# SurfaceEEG_V1_2.net
KiCad netlist of a schematic drawn in EAGLE
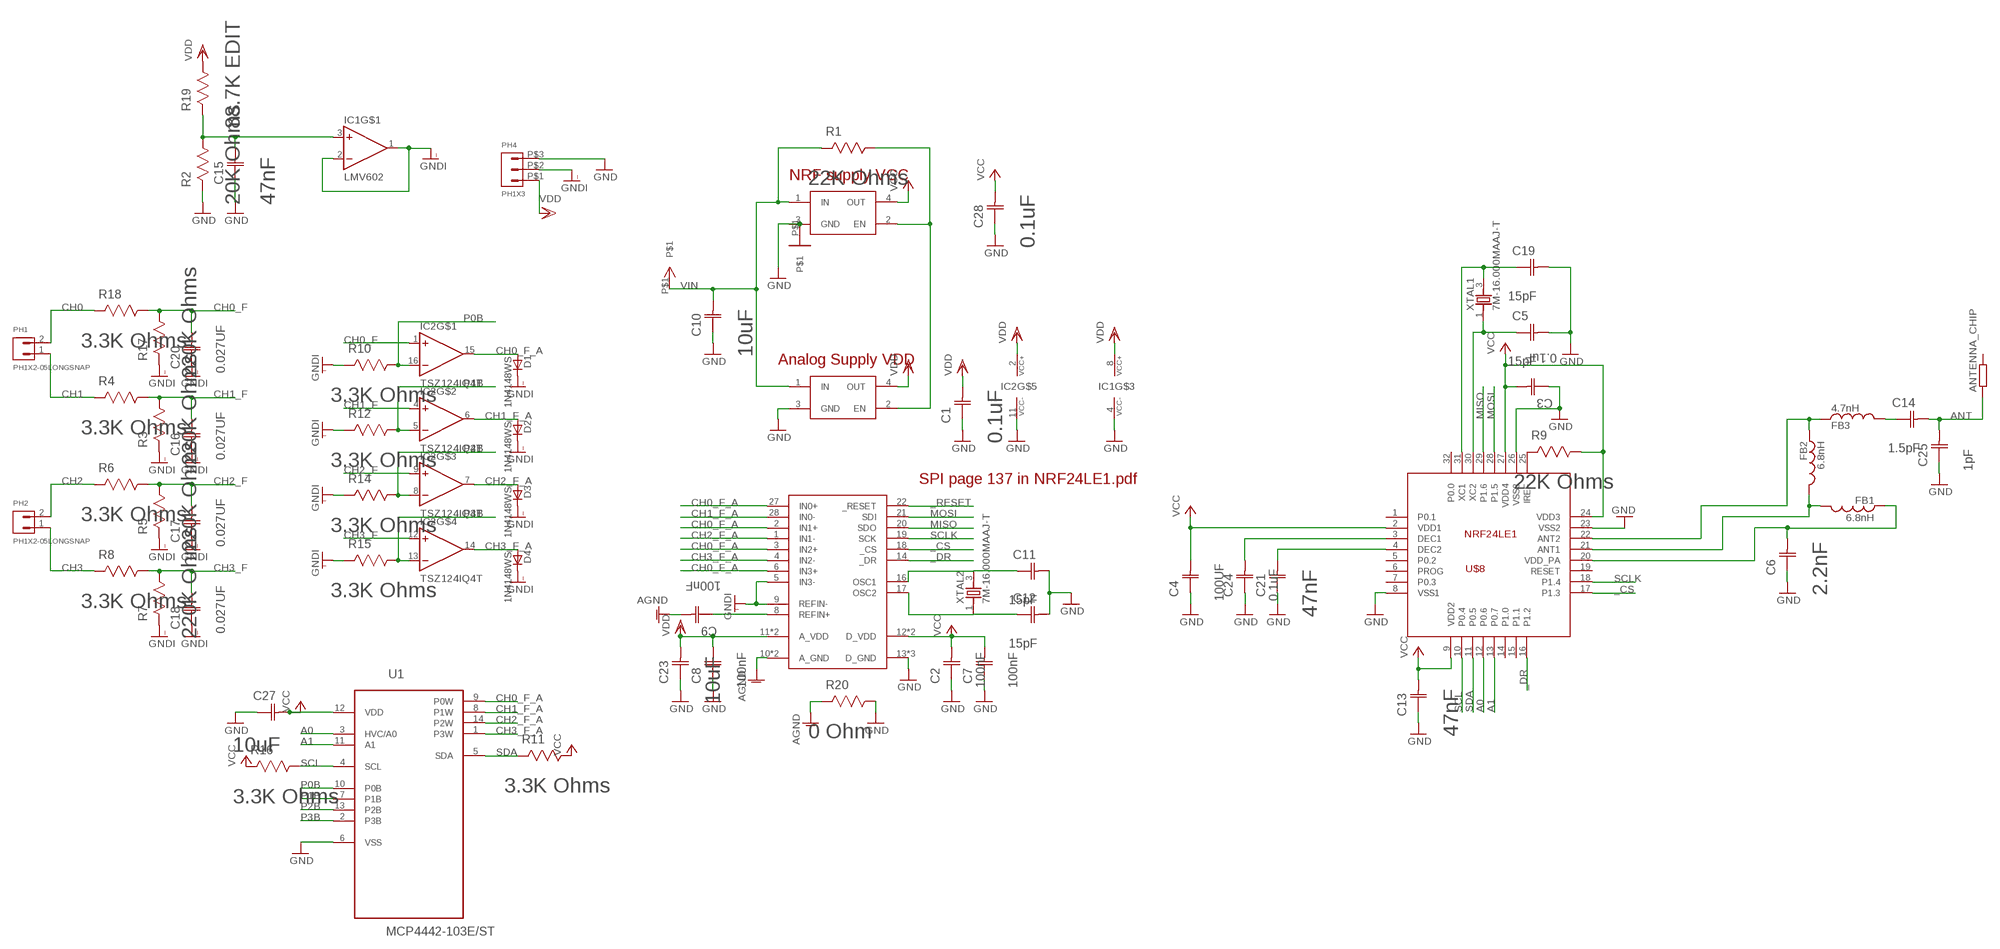
[diagram p0: schematic, sheet 1]

(export (version "E")
  (design (tool "Eeschema 10.0.6"))
  (components
    (comp (ref "ANTENNA_CHIP")
      (value "R0805")
      (footprint "eagle-import:R0805")
      (libsource (lib "eagle-import") (part "R0805"))
    )
    (comp (ref "C1")
      (value "0.1uF")
      (footprint "eagle-import:CAPC1608X85N")
      (fields (field (name "MPN") "C0603C104K5RAC-TU") (field (name "TOLERANCE") "±10%"))
      (libsource (lib "eagle-import") (part "C0603C104K5RAC-TU"))
    )
    (comp (ref "C2")
      (value "100nF")
      (footprint "eagle-import:CAPC1608X90N")
      (fields (field (name "MPN") "06033C104JAT2A") (field (name "TOLERANCE") "±5%"))
      (libsource (lib "eagle-import") (part "06033C104JAT2A"))
    )
    (comp (ref "C3")
      (value "0.1uF")
      (footprint "eagle-import:CAPC1005X60N")
      (fields (field (name "MPN") "04023C104KAT2A") (field (name "TOLERANCE") "±10%"))
      (libsource (lib "eagle-import") (part "04023C104KAT2A"))
    )
    (comp (ref "C4")
      (value "100UF")
      (footprint "eagle-import:CAPC3216X178N")
      (fields (field (name "MPN") "1206YD106MAT2A") (field (name "TOLERANCE") "±20%"))
      (libsource (lib "eagle-import") (part "1206YD106MAT2A"))
    )
    (comp (ref "C5")
      (value "15pF")
      (footprint "eagle-import:CAPC1005X60N")
      (fields (field (name "MPN") "UQCL2A150JAT2A/500") (field (name "TOLERANCE") "±5%"))
      (libsource (lib "eagle-import") (part "UQCL2A150JAT2A/500"))
    )
    (comp (ref "C6")
      (value "2.2nF")
      (footprint "eagle-import:CAPC1005X60N")
      (fields (field (name "MPN") "C0402C222K5RACTU") (field (name "TOLERANCE") "±10%"))
      (libsource (lib "eagle-import") (part "C0402C222K5RACTU"))
    )
    (comp (ref "C7")
      (value "100nF")
      (footprint "eagle-import:CAPC1608X90N")
      (fields (field (name "MPN") "06033C104JAT2A") (field (name "TOLERANCE") "±5%"))
      (libsource (lib "eagle-import") (part "06033C104JAT2A"))
    )
    (comp (ref "C8")
      (value "100nF")
      (footprint "eagle-import:CAPC1608X90N")
      (fields (field (name "MPN") "06033C104JAT2A") (field (name "TOLERANCE") "±5%"))
      (libsource (lib "eagle-import") (part "06033C104JAT2A"))
    )
    (comp (ref "C9")
      (value "100nF")
      (footprint "eagle-import:CAPC1608X90N")
      (fields (field (name "MPN") "06033C104JAT2A") (field (name "TOLERANCE") "±5%"))
      (libsource (lib "eagle-import") (part "06033C104JAT2A"))
    )
    (comp (ref "C10")
      (value "10uF")
      (footprint "eagle-import:CAPC1608X85N")
      (fields (field (name "MPN") "C0603C106M9PACTU") (field (name "TOLERANCE") "±20%"))
      (libsource (lib "eagle-import") (part "C0603C106M9PACTU"))
    )
    (comp (ref "C11")
      (value "15pF")
      (footprint "eagle-import:CAPC1005X60N")
      (fields (field (name "MPN") "UQCL2A150JAT2A/500") (field (name "TOLERANCE") "±5%"))
      (libsource (lib "eagle-import") (part "UQCL2A150JAT2A/500"))
    )
    (comp (ref "C12")
      (value "15pF")
      (footprint "eagle-import:CAPC1005X60N")
      (fields (field (name "MPN") "UQCL2A150JAT2A/500") (field (name "TOLERANCE") "±5%"))
      (libsource (lib "eagle-import") (part "UQCL2A150JAT2A/500"))
    )
    (comp (ref "C13")
      (value "47nF")
      (footprint "eagle-import:CAPC1608X85N")
      (fields (field (name "MPN") "C0603C473K1RACTU") (field (name "TOLERANCE") "±10%"))
      (libsource (lib "eagle-import") (part "C0603C473K1RACTU"))
    )
    (comp (ref "C14")
      (value "1.5pF")
      (footprint "eagle-import:CAPC1005X60N")
      (fields (field (name "MPN") "UQCL2A1R5BAT2A/500") (field (name "TOLERANCE") "±.1 pF"))
      (libsource (lib "eagle-import") (part "UQCL2A1R5BAT2A/500"))
    )
    (comp (ref "C15")
      (value "47nF")
      (footprint "eagle-import:CAPC1608X85N")
      (fields (field (name "MPN") "C0603C473K1RACTU") (field (name "TOLERANCE") "±10%"))
      (libsource (lib "eagle-import") (part "C0603C473K1RACTU"))
    )
    (comp (ref "C16")
      (value "0.027UF")
      (footprint "eagle-import:CAPC1608X90N")
      (fields (field (name "MPN") "0603YC273JAT2A") (field (name "TOLERANCE") "±5%"))
      (libsource (lib "eagle-import") (part "0603YC273JAT2A"))
    )
    (comp (ref "C17")
      (value "0.027UF")
      (footprint "eagle-import:CAPC1608X90N")
      (fields (field (name "MPN") "0603YC273JAT2A") (field (name "TOLERANCE") "±5%"))
      (libsource (lib "eagle-import") (part "0603YC273JAT2A"))
    )
    (comp (ref "C18")
      (value "0.027UF")
      (footprint "eagle-import:CAPC1608X90N")
      (fields (field (name "MPN") "0603YC273JAT2A") (field (name "TOLERANCE") "±5%"))
      (libsource (lib "eagle-import") (part "0603YC273JAT2A"))
    )
    (comp (ref "C19")
      (value "15pF")
      (footprint "eagle-import:CAPC1005X60N")
      (fields (field (name "MPN") "UQCL2A150JAT2A/500") (field (name "TOLERANCE") "±5%"))
      (libsource (lib "eagle-import") (part "UQCL2A150JAT2A/500"))
    )
    (comp (ref "C20")
      (value "0.027UF")
      (footprint "eagle-import:CAPC1608X90N")
      (fields (field (name "MPN") "0603YC273JAT2A") (field (name "TOLERANCE") "±5%"))
      (libsource (lib "eagle-import") (part "0603YC273JAT2A"))
    )
    (comp (ref "C21")
      (value "47nF")
      (footprint "eagle-import:CAPC1608X85N")
      (fields (field (name "MPN") "C0603C473K1RACTU") (field (name "TOLERANCE") "±10%"))
      (libsource (lib "eagle-import") (part "C0603C473K1RACTU"))
    )
    (comp (ref "C23")
      (value "10uF")
      (footprint "eagle-import:CAPC1608X85N")
      (fields (field (name "MPN") "C0603C106M9PACTU") (field (name "TOLERANCE") "±20%"))
      (libsource (lib "eagle-import") (part "C0603C106M9PACTU"))
    )
    (comp (ref "C24")
      (value "0.1uF")
      (footprint "eagle-import:CAPC1005X60N")
      (fields (field (name "MPN") "04023C104KAT2A") (field (name "TOLERANCE") "±10%"))
      (libsource (lib "eagle-import") (part "04023C104KAT2A"))
    )
    (comp (ref "C25")
      (value "1pF")
      (footprint "eagle-import:CAPC1005X60N")
      (fields (field (name "MPN") "UQCL2A1R0BAT2A/500") (field (name "TOLERANCE") "±.1 pF"))
      (libsource (lib "eagle-import") (part "UQCL2A1R0BAT2A/500"))
    )
    (comp (ref "C27")
      (value "10uF")
      (footprint "eagle-import:CAPC1608X85N")
      (fields (field (name "MPN") "C0603C106M9PACTU") (field (name "TOLERANCE") "±20%"))
      (libsource (lib "eagle-import") (part "C0603C106M9PACTU"))
    )
    (comp (ref "C28")
      (value "0.1uF")
      (footprint "eagle-import:CAPC1608X85N")
      (fields (field (name "MPN") "C0603C104K5RAC-TU") (field (name "TOLERANCE") "±10%"))
      (libsource (lib "eagle-import") (part "C0603C104K5RAC-TU"))
    )
    (comp (ref "D1")
      (value "1N4148WS")
      (footprint "eagle-import:SOD323F")
      (libsource (lib "eagle-import") (part "1N4148WS"))
    )
    (comp (ref "D2")
      (value "1N4148WS")
      (footprint "eagle-import:SOD323F")
      (libsource (lib "eagle-import") (part "1N4148WS"))
    )
    (comp (ref "D3")
      (value "1N4148WS")
      (footprint "eagle-import:SOD323F")
      (libsource (lib "eagle-import") (part "1N4148WS"))
    )
    (comp (ref "D4")
      (value "1N4148WS")
      (footprint "eagle-import:SOD323F")
      (libsource (lib "eagle-import") (part "1N4148WS"))
    )
    (comp (ref "FB1")
      (value "6.8nH")
      (footprint "eagle-import:FB0402")
      (libsource (lib "eagle-import") (part "FB0402"))
    )
    (comp (ref "FB2")
      (value "6.8nH")
      (footprint "eagle-import:FB0402")
      (libsource (lib "eagle-import") (part "FB0402"))
    )
    (comp (ref "FB3")
      (value "4.7nH")
      (footprint "eagle-import:FB0402")
      (libsource (lib "eagle-import") (part "FB0402"))
    )
    (comp (ref "IC1")
      (value "LMV602")
      (footprint "eagle-import:VSSOP8")
      (fields (field (name "MPN") "LMV602MM/NOPB"))
      (libsource (lib "eagle-import") (part "LMV602"))
    )
    (comp (ref "IC2")
      (value "TSZ124IQ4T")
      (footprint "eagle-import:QFN16")
      (libsource (lib "eagle-import") (part "TSZ124IQ4T"))
    )
    (comp (ref "PH1")
      (value "PH1X2-05LONGSNAP")
      (footprint "eagle-import:PHLS005-1-2")
      (libsource (lib "eagle-import") (part "PH1X2-05LONGSNAP"))
    )
    (comp (ref "PH2")
      (value "PH1X2-05LONGSNAP")
      (footprint "eagle-import:PHLS005-1-2")
      (libsource (lib "eagle-import") (part "PH1X2-05LONGSNAP"))
    )
    (comp (ref "PH4")
      (value "PH1X3")
      (footprint "eagle-import:PH005-1-3")
      (libsource (lib "eagle-import") (part "PH1X3"))
    )
    (comp (ref "R1")
      (value "22K Ohms")
      (footprint "eagle-import:RESC1608X60N")
      (fields (field (name "MPN") "RC0603FR-0722KL") (field (name "TOLERANCE") "±1%"))
      (libsource (lib "eagle-import") (part "RC0603FR-0722KL"))
    )
    (comp (ref "R2")
      (value "20K Ohms")
      (footprint "eagle-import:RESC1608X60N")
      (fields (field (name "MPN") "RC0603FR-0720KL") (field (name "TOLERANCE") "±1%"))
      (libsource (lib "eagle-import") (part "RC0603FR-0720KL"))
    )
    (comp (ref "R3")
      (value "220K Ohms")
      (footprint "eagle-import:RESC1608X60N")
      (fields (field (name "MPN") "RC0603FR-07220KL") (field (name "TOLERANCE") "±1%"))
      (libsource (lib "eagle-import") (part "RC0603FR-07220KL"))
    )
    (comp (ref "R4")
      (value "3.3K Ohms")
      (footprint "eagle-import:RESC1608X60N")
      (fields (field (name "MPN") "RC0603FR-073K3L") (field (name "TOLERANCE") "±1%"))
      (libsource (lib "eagle-import") (part "RC0603FR-073K3L"))
    )
    (comp (ref "R5")
      (value "220K Ohms")
      (footprint "eagle-import:RESC1608X60N")
      (fields (field (name "MPN") "RC0603FR-07220KL") (field (name "TOLERANCE") "±1%"))
      (libsource (lib "eagle-import") (part "RC0603FR-07220KL"))
    )
    (comp (ref "R6")
      (value "3.3K Ohms")
      (footprint "eagle-import:RESC1608X60N")
      (fields (field (name "MPN") "RC0603FR-073K3L") (field (name "TOLERANCE") "±1%"))
      (libsource (lib "eagle-import") (part "RC0603FR-073K3L"))
    )
    (comp (ref "R7")
      (value "220K Ohms")
      (footprint "eagle-import:RESC1608X60N")
      (fields (field (name "MPN") "RC0603FR-07220KL") (field (name "TOLERANCE") "±1%"))
      (libsource (lib "eagle-import") (part "RC0603FR-07220KL"))
    )
    (comp (ref "R8")
      (value "3.3K Ohms")
      (footprint "eagle-import:RESC1608X60N")
      (fields (field (name "MPN") "RC0603FR-073K3L") (field (name "TOLERANCE") "±1%"))
      (libsource (lib "eagle-import") (part "RC0603FR-073K3L"))
    )
    (comp (ref "R9")
      (value "22K Ohms")
      (footprint "eagle-import:RESC1608X60N")
      (fields (field (name "MPN") "RC0603FR-0722KL") (field (name "TOLERANCE") "±1%"))
      (libsource (lib "eagle-import") (part "RC0603FR-0722KL"))
    )
    (comp (ref "R10")
      (value "3.3K Ohms")
      (footprint "eagle-import:RESC1608X60N")
      (fields (field (name "MPN") "RC0603FR-073K3L") (field (name "TOLERANCE") "±1%"))
      (libsource (lib "eagle-import") (part "RC0603FR-073K3L"))
    )
    (comp (ref "R11")
      (value "3.3K Ohms")
      (footprint "eagle-import:RESC1608X60N")
      (fields (field (name "MPN") "RC0603FR-073K3L") (field (name "TOLERANCE") "±1%"))
      (libsource (lib "eagle-import") (part "RC0603FR-073K3L"))
    )
    (comp (ref "R12")
      (value "3.3K Ohms")
      (footprint "eagle-import:RESC1608X60N")
      (fields (field (name "MPN") "RC0603FR-073K3L") (field (name "TOLERANCE") "±1%"))
      (libsource (lib "eagle-import") (part "RC0603FR-073K3L"))
    )
    (comp (ref "R14")
      (value "3.3K Ohms")
      (footprint "eagle-import:RESC1608X60N")
      (fields (field (name "MPN") "RC0603FR-073K3L") (field (name "TOLERANCE") "±1%"))
      (libsource (lib "eagle-import") (part "RC0603FR-073K3L"))
    )
    (comp (ref "R15")
      (value "3.3K Ohms")
      (footprint "eagle-import:RESC1608X60N")
      (fields (field (name "MPN") "RC0603FR-073K3L") (field (name "TOLERANCE") "±1%"))
      (libsource (lib "eagle-import") (part "RC0603FR-073K3L"))
    )
    (comp (ref "R16")
      (value "3.3K Ohms")
      (footprint "eagle-import:RESC1608X60N")
      (fields (field (name "MPN") "RC0603FR-073K3L") (field (name "TOLERANCE") "±1%"))
      (libsource (lib "eagle-import") (part "RC0603FR-073K3L"))
    )
    (comp (ref "R17")
      (value "220K Ohms")
      (footprint "eagle-import:RESC1608X60N")
      (fields (field (name "MPN") "RC0603FR-07220KL") (field (name "TOLERANCE") "±1%"))
      (libsource (lib "eagle-import") (part "RC0603FR-07220KL"))
    )
    (comp (ref "R18")
      (value "3.3K Ohms")
      (footprint "eagle-import:RESC1608X60N")
      (fields (field (name "MPN") "RC0603FR-073K3L") (field (name "TOLERANCE") "±1%"))
      (libsource (lib "eagle-import") (part "RC0603FR-073K3L"))
    )
    (comp (ref "R19")
      (value "88.7K EDIT")
      (footprint "eagle-import:RESC1608X60N")
      (fields (field (name "MPN") "RT0603FRE0782KL") (field (name "TOLERANCE") "±1%"))
      (libsource (lib "eagle-import") (part "RT0603FRE0782KL"))
    )
    (comp (ref "R20")
      (value "0 Ohm")
      (footprint "eagle-import:RESC1608X60N")
      (fields (field (name "MPN") "9C06031A0R00JLHFT") (field (name "TOLERANCE") "±5%"))
      (libsource (lib "eagle-import") (part "9C06031A0R00JLHFT"))
    )
    (comp (ref "U$1")
      (value "NCP103")
      (footprint "eagle-import:UDFN4-1_1")
      (fields (field (name "MPN") "NCP103AMX330TCG"))
      (libsource (lib "eagle-import") (part "NCP103"))
    )
    (comp (ref "U$2")
      (value "NCP103")
      (footprint "eagle-import:UDFN4-1_1")
      (fields (field (name "MPN") "NCP103AMX330TCG"))
      (libsource (lib "eagle-import") (part "NCP103"))
    )
    (comp (ref "U$3")
      (value "MCP3912")
      (footprint "eagle-import:QFN28")
      (fields (field (name "MPN") "MCP3912A1-E/MQ "))
      (libsource (lib "eagle-import") (part "MCP3912"))
    )
    (comp (ref "U$4")
      (value "VCC")
      (footprint "eagle-import:VCC-PAD")
      (libsource (lib "eagle-import") (part "VCC"))
    )
    (comp (ref "U$5")
      (value "GND")
      (footprint "eagle-import:GND-PAD")
      (libsource (lib "eagle-import") (part "GND"))
    )
    (comp (ref "U$8")
      (value "NRF24LE1")
      (footprint "eagle-import:QFN-32")
      (fields (field (name "MPN") "NRF24LE1-F16Q24-T"))
      (libsource (lib "eagle-import") (part "NRF24LE1"))
    )
    (comp (ref "U1")
      (value "MCP4442-103E/ST")
      (footprint "eagle-import:SOP65P640X120-14N")
      (libsource (lib "eagle-import") (part "MCP4442-103E/ST"))
    )
    (comp (ref "XTAL1")
      (value "7M-16.000MAAJ-T")
      (footprint "eagle-import:TXC_7M-16.000MAAJ-T")
      (fields (field (name "MPN") "7M-16.000MAAJ-T "))
      (libsource (lib "eagle-import") (part "7M-16.000MAAJ-T"))
    )
    (comp (ref "XTAL2")
      (value "7M-16.000MAAJ-T")
      (footprint "eagle-import:TXC_7M-16.000MAAJ-T")
      (fields (field (name "MPN") "7M-16.000MAAJ-T "))
      (libsource (lib "eagle-import") (part "7M-16.000MAAJ-T"))
    )
  )
  (nets
    (net (code "1") (name "/A0") (class "Default")
      (node (ref "U$8") (pin "12") (pinfunction "P0.6_12") (pintype "bidirectional"))
      (node (ref "U1") (pin "3") (pinfunction "HVC/A0_3") (pintype "input"))
    )
    (net (code "2") (name "/A1") (class "Default")
      (node (ref "U$8") (pin "13") (pinfunction "P0.7_13") (pintype "bidirectional"))
      (node (ref "U1") (pin "11") (pinfunction "A1_11") (pintype "input"))
    )
    (net (code "3") (name "/ANT") (class "Default")
      (node (ref "ANTENNA_CHIP") (pin "1") (pinfunction "1_1") (pintype "passive"))
      (node (ref "C14") (pin "1") (pinfunction "C2_1") (pintype "passive"))
      (node (ref "C25") (pin "1") (pinfunction "C2_1") (pintype "passive"))
    )
    (net (code "4") (name "/CH0") (class "Default")
      (node (ref "PH1") (pin "2") (pinfunction "2_2") (pintype "bidirectional"))
      (node (ref "R18") (pin "2") (pinfunction "R2_2") (pintype "passive"))
    )
    (net (code "5") (name "/CH0_F") (class "Default")
      (node (ref "C20") (pin "2") (pinfunction "C2_2") (pintype "passive"))
      (node (ref "IC2") (pin "1") (pinfunction "IN+_1") (pintype "input"))
      (node (ref "R17") (pin "1") (pinfunction "R1_1") (pintype "passive"))
      (node (ref "R18") (pin "1") (pinfunction "R1_1") (pintype "passive"))
    )
    (net (code "6") (name "/CH0_F_A") (class "Default")
      (node (ref "D1") (pin "A") (pinfunction "A_A") (pintype "passive"))
      (node (ref "IC2") (pin "15") (pinfunction "OUT_15") (pintype "output"))
      (node (ref "U$3") (pin "2") (pinfunction "IN1+_2") (pintype "bidirectional"))
      (node (ref "U$3") (pin "27") (pinfunction "IN0+_27") (pintype "bidirectional"))
      (node (ref "U$3") (pin "3") (pinfunction "IN2+_3") (pintype "bidirectional"))
      (node (ref "U$3") (pin "6") (pinfunction "IN3+_6") (pintype "bidirectional"))
      (node (ref "U1") (pin "9") (pinfunction "P0W_9") (pintype "passive"))
    )
    (net (code "7") (name "/CH1") (class "Default")
      (node (ref "PH1") (pin "1") (pinfunction "1_1") (pintype "bidirectional"))
      (node (ref "R4") (pin "2") (pinfunction "R2_2") (pintype "passive"))
    )
    (net (code "8") (name "/CH1_F") (class "Default")
      (node (ref "C16") (pin "2") (pinfunction "C2_2") (pintype "passive"))
      (node (ref "IC2") (pin "4") (pinfunction "IN+_4") (pintype "input"))
      (node (ref "R3") (pin "1") (pinfunction "R1_1") (pintype "passive"))
      (node (ref "R4") (pin "1") (pinfunction "R1_1") (pintype "passive"))
    )
    (net (code "9") (name "/CH1_F_A") (class "Default")
      (node (ref "D2") (pin "A") (pinfunction "A_A") (pintype "passive"))
      (node (ref "IC2") (pin "6") (pinfunction "OUT_6") (pintype "output"))
      (node (ref "U$3") (pin "28") (pinfunction "IN0-_28") (pintype "bidirectional"))
      (node (ref "U1") (pin "8") (pinfunction "P1W_8") (pintype "passive"))
    )
    (net (code "10") (name "/CH2") (class "Default")
      (node (ref "PH2") (pin "2") (pinfunction "2_2") (pintype "bidirectional"))
      (node (ref "R6") (pin "2") (pinfunction "R2_2") (pintype "passive"))
    )
    (net (code "11") (name "/CH2_F") (class "Default")
      (node (ref "C17") (pin "2") (pinfunction "C2_2") (pintype "passive"))
      (node (ref "IC2") (pin "9") (pinfunction "IN+_9") (pintype "input"))
      (node (ref "R5") (pin "1") (pinfunction "R1_1") (pintype "passive"))
      (node (ref "R6") (pin "1") (pinfunction "R1_1") (pintype "passive"))
    )
    (net (code "12") (name "/CH2_F_A") (class "Default")
      (node (ref "D3") (pin "A") (pinfunction "A_A") (pintype "passive"))
      (node (ref "IC2") (pin "7") (pinfunction "OUT_7") (pintype "output"))
      (node (ref "U$3") (pin "1") (pinfunction "IN1-_1") (pintype "bidirectional"))
      (node (ref "U1") (pin "14") (pinfunction "P2W_14") (pintype "passive"))
    )
    (net (code "13") (name "/CH3") (class "Default")
      (node (ref "PH2") (pin "1") (pinfunction "1_1") (pintype "bidirectional"))
      (node (ref "R8") (pin "2") (pinfunction "R2_2") (pintype "passive"))
    )
    (net (code "14") (name "/CH3_F") (class "Default")
      (node (ref "C18") (pin "2") (pinfunction "C2_2") (pintype "passive"))
      (node (ref "IC2") (pin "12") (pinfunction "IN+_12") (pintype "input"))
      (node (ref "R7") (pin "1") (pinfunction "R1_1") (pintype "passive"))
      (node (ref "R8") (pin "1") (pinfunction "R1_1") (pintype "passive"))
    )
    (net (code "15") (name "/CH3_F_A") (class "Default")
      (node (ref "D4") (pin "A") (pinfunction "A_A") (pintype "passive"))
      (node (ref "IC2") (pin "14") (pinfunction "OUT_14") (pintype "output"))
      (node (ref "U$3") (pin "4") (pinfunction "IN2-_4") (pintype "bidirectional"))
      (node (ref "U1") (pin "1") (pinfunction "P3W_1") (pintype "passive"))
    )
    (net (code "16") (name "/MISO") (class "Default")
      (node (ref "U$3") (pin "20") (pinfunction "SDO_20") (pintype "bidirectional"))
      (node (ref "U$8") (pin "29") (pinfunction "P1.6_29") (pintype "bidirectional"))
    )
    (net (code "17") (name "/MOSI") (class "Default")
      (node (ref "U$3") (pin "21") (pinfunction "SDI_21") (pintype "bidirectional"))
      (node (ref "U$8") (pin "28") (pinfunction "P1.5_28") (pintype "bidirectional"))
    )
    (net (code "18") (name "/P0B") (class "Default")
      (node (ref "IC2") (pin "16") (pinfunction "IN-_16") (pintype "input"))
      (node (ref "R10") (pin "1") (pinfunction "R1_1") (pintype "passive"))
      (node (ref "U1") (pin "10") (pinfunction "P0B_10") (pintype "passive"))
    )
    (net (code "19") (name "/P1B") (class "Default")
      (node (ref "IC2") (pin "5") (pinfunction "IN-_5") (pintype "input"))
      (node (ref "R12") (pin "1") (pinfunction "R1_1") (pintype "passive"))
      (node (ref "U1") (pin "7") (pinfunction "P1B_7") (pintype "passive"))
    )
    (net (code "20") (name "/P2B") (class "Default")
      (node (ref "IC2") (pin "8") (pinfunction "IN-_8") (pintype "input"))
      (node (ref "R14") (pin "1") (pinfunction "R1_1") (pintype "passive"))
      (node (ref "U1") (pin "13") (pinfunction "P2B_13") (pintype "passive"))
    )
    (net (code "21") (name "/P3B") (class "Default")
      (node (ref "IC2") (pin "13") (pinfunction "IN-_13") (pintype "input"))
      (node (ref "R15") (pin "1") (pinfunction "R1_1") (pintype "passive"))
      (node (ref "U1") (pin "2") (pinfunction "P3B_2") (pintype "passive"))
    )
    (net (code "22") (name "/SCL") (class "Default")
      (node (ref "R16") (pin "1") (pinfunction "R1_1") (pintype "passive"))
      (node (ref "U$8") (pin "10") (pinfunction "P0.4_10") (pintype "bidirectional"))
      (node (ref "U1") (pin "4") (pinfunction "SCL_4") (pintype "input"))
    )
    (net (code "23") (name "/SCLK") (class "Default")
      (node (ref "U$3") (pin "19") (pinfunction "SCK_19") (pintype "bidirectional"))
      (node (ref "U$8") (pin "18") (pinfunction "P1.4_18") (pintype "bidirectional"))
    )
    (net (code "24") (name "/SDA") (class "Default")
      (node (ref "R11") (pin "2") (pinfunction "R2_2") (pintype "passive"))
      (node (ref "U$8") (pin "11") (pinfunction "P0.5_11") (pintype "bidirectional"))
      (node (ref "U1") (pin "5") (pinfunction "SDA_5") (pintype "bidirectional"))
    )
    (net (code "25") (name "/VIN") (class "Default")
      (node (ref "C10") (pin "2") (pinfunction "C2_2") (pintype "passive"))
      (node (ref "R1") (pin "2") (pinfunction "R2_2") (pintype "passive"))
      (node (ref "U$1") (pin "1") (pinfunction "IN_1") (pintype "bidirectional"))
      (node (ref "U$2") (pin "1") (pinfunction "IN_1") (pintype "bidirectional"))
      (node (ref "U$4") (pin "P$1") (pinfunction "P$1_P$1") (pintype "bidirectional"))
    )
    (net (code "26") (name "/_CS") (class "Default")
      (node (ref "U$3") (pin "18") (pinfunction "_CS_18") (pintype "bidirectional"))
      (node (ref "U$8") (pin "17") (pinfunction "P1.3_17") (pintype "bidirectional"))
    )
    (net (code "27") (name "/_DR") (class "Default")
      (node (ref "U$3") (pin "14") (pinfunction "_DR_14") (pintype "bidirectional"))
      (node (ref "U$8") (pin "16") (pinfunction "P1.2_16") (pintype "bidirectional"))
    )
    (net (code "28") (name "/_RESET") (class "Default")
      (node (ref "U$3") (pin "22") (pinfunction "_RESET_22") (pintype "bidirectional"))
    )
    (net (code "29") (name "AGND") (class "Default")
      (node (ref "C9") (pin "2") (pinfunction "C2_2") (pintype "passive"))
      (node (ref "R20") (pin "2") (pinfunction "R2_2") (pintype "passive"))
      (node (ref "U$3") (pin "10") (pinfunction "A_GND_10") (pintype "bidirectional"))
      (node (ref "U$3") (pin "26") (pinfunction "A_GND_26") (pintype "bidirectional"))
    )
    (net (code "30") (name "GND") (class "Default")
      (node (ref "C1") (pin "1") (pinfunction "C1_1") (pintype "passive"))
      (node (ref "C10") (pin "1") (pinfunction "C1_1") (pintype "passive"))
      (node (ref "C11") (pin "1") (pinfunction "C2_1") (pintype "passive"))
      (node (ref "C12") (pin "1") (pinfunction "C2_1") (pintype "passive"))
      (node (ref "C13") (pin "1") (pinfunction "C1_1") (pintype "passive"))
      (node (ref "C15") (pin "1") (pinfunction "C1_1") (pintype "passive"))
      (node (ref "C19") (pin "1") (pinfunction "C2_1") (pintype "passive"))
      (node (ref "C2") (pin "1") (pinfunction "C1_1") (pintype "passive"))
      (node (ref "C21") (pin "1") (pinfunction "C1_1") (pintype "passive"))
      (node (ref "C23") (pin "1") (pinfunction "C1_1") (pintype "passive"))
      (node (ref "C24") (pin "2") (pinfunction "C1_2") (pintype "passive"))
      (node (ref "C25") (pin "2") (pinfunction "C1_2") (pintype "passive"))
      (node (ref "C27") (pin "1") (pinfunction "C1_1") (pintype "passive"))
      (node (ref "C28") (pin "1") (pinfunction "C1_1") (pintype "passive"))
      (node (ref "C3") (pin "2") (pinfunction "C1_2") (pintype "passive"))
      (node (ref "C4") (pin "1") (pinfunction "C1_1") (pintype "passive"))
      (node (ref "C5") (pin "1") (pinfunction "C2_1") (pintype "passive"))
      (node (ref "C6") (pin "1") (pinfunction "C1_1") (pintype "passive"))
      (node (ref "C7") (pin "1") (pinfunction "C1_1") (pintype "passive"))
      (node (ref "C8") (pin "1") (pinfunction "C1_1") (pintype "passive"))
      (node (ref "IC1") (pin "4") (pinfunction "VCC-_4") (pintype "power_in"))
      (node (ref "IC2") (pin "11") (pinfunction "VCC-_11") (pintype "power_in"))
      (node (ref "PH4") (pin "P$3") (pinfunction "3_P$3") (pintype "bidirectional"))
      (node (ref "R2") (pin "2") (pinfunction "R2_2") (pintype "passive"))
      (node (ref "R20") (pin "1") (pinfunction "R1_1") (pintype "passive"))
      (node (ref "U$1") (pin "3") (pinfunction "GND_3") (pintype "bidirectional"))
      (node (ref "U$2") (pin "3") (pinfunction "GND_3") (pintype "bidirectional"))
      (node (ref "U$3") (pin "13") (pinfunction "D_GND_13") (pintype "bidirectional"))
      (node (ref "U$3") (pin "15") (pinfunction "D_GND_15") (pintype "bidirectional"))
      (node (ref "U$3") (pin "23") (pinfunction "D_GND_23") (pintype "bidirectional"))
      (node (ref "U$5") (pin "P$1") (pinfunction "P$1_P$1") (pintype "bidirectional"))
      (node (ref "U$8") (pin "23") (pinfunction "VSS2_23") (pintype "bidirectional"))
      (node (ref "U$8") (pin "26") (pinfunction "VSS3_26") (pintype "bidirectional"))
      (node (ref "U$8") (pin "8") (pinfunction "VSS1_8") (pintype "bidirectional"))
      (node (ref "U1") (pin "6") (pinfunction "VSS_6") (pintype "power_in"))
    )
    (net (code "31") (name "GNDI") (class "Default")
      (node (ref "C16") (pin "1") (pinfunction "C1_1") (pintype "passive"))
      (node (ref "C17") (pin "1") (pinfunction "C1_1") (pintype "passive"))
      (node (ref "C18") (pin "1") (pinfunction "C1_1") (pintype "passive"))
      (node (ref "C20") (pin "1") (pinfunction "C1_1") (pintype "passive"))
      (node (ref "D1") (pin "C") (pinfunction "C_C") (pintype "passive"))
      (node (ref "D2") (pin "C") (pinfunction "C_C") (pintype "passive"))
      (node (ref "D3") (pin "C") (pinfunction "C_C") (pintype "passive"))
      (node (ref "D4") (pin "C") (pinfunction "C_C") (pintype "passive"))
      (node (ref "IC1") (pin "1") (pinfunction "OUT_1") (pintype "output"))
      (node (ref "IC1") (pin "2") (pinfunction "IN-_2") (pintype "input"))
      (node (ref "PH4") (pin "P$2") (pinfunction "2_P$2") (pintype "bidirectional"))
      (node (ref "R10") (pin "2") (pinfunction "R2_2") (pintype "passive"))
      (node (ref "R12") (pin "2") (pinfunction "R2_2") (pintype "passive"))
      (node (ref "R14") (pin "2") (pinfunction "R2_2") (pintype "passive"))
      (node (ref "R15") (pin "2") (pinfunction "R2_2") (pintype "passive"))
      (node (ref "R17") (pin "2") (pinfunction "R2_2") (pintype "passive"))
      (node (ref "R3") (pin "2") (pinfunction "R2_2") (pintype "passive"))
      (node (ref "R5") (pin "2") (pinfunction "R2_2") (pintype "passive"))
      (node (ref "R7") (pin "2") (pinfunction "R2_2") (pintype "passive"))
      (node (ref "U$3") (pin "5") (pinfunction "IN3-_5") (pintype "bidirectional"))
      (node (ref "U$3") (pin "9") (pinfunction "REFIN-_9") (pintype "bidirectional"))
    )
    (net (code "32") (name "Net-(C5-C1)") (class "Default")
      (node (ref "C5") (pin "2") (pinfunction "C1_2") (pintype "passive"))
      (node (ref "U$8") (pin "30") (pinfunction "XC2_30") (pintype "bidirectional"))
      (node (ref "XTAL1") (pin "1") (pinfunction "1_1") (pintype "passive"))
    )
    (net (code "33") (name "Net-(C6-C2)") (class "Default")
      (node (ref "C6") (pin "2") (pinfunction "C2_2") (pintype "passive"))
      (node (ref "FB1") (pin "1") (pinfunction "1_1") (pintype "passive"))
      (node (ref "U$8") (pin "20") (pinfunction "VDD_PA_20") (pintype "bidirectional"))
    )
    (net (code "34") (name "Net-(C9-C1)") (class "Default")
      (node (ref "C9") (pin "1") (pinfunction "C1_1") (pintype "passive"))
      (node (ref "U$3") (pin "8") (pinfunction "REFIN+_8") (pintype "bidirectional"))
    )
    (net (code "35") (name "Net-(C11-C1)") (class "Default")
      (node (ref "C11") (pin "2") (pinfunction "C1_2") (pintype "passive"))
      (node (ref "U$3") (pin "16") (pinfunction "OSC1_16") (pintype "bidirectional"))
      (node (ref "XTAL2") (pin "3") (pinfunction "3_3") (pintype "passive"))
    )
    (net (code "36") (name "Net-(C12-C1)") (class "Default")
      (node (ref "C12") (pin "2") (pinfunction "C1_2") (pintype "passive"))
      (node (ref "U$3") (pin "17") (pinfunction "OSC2_17") (pintype "bidirectional"))
      (node (ref "XTAL2") (pin "1") (pinfunction "1_1") (pintype "passive"))
    )
    (net (code "37") (name "Net-(C14-C1)") (class "Default")
      (node (ref "C14") (pin "2") (pinfunction "C1_2") (pintype "passive"))
      (node (ref "FB3") (pin "2") (pinfunction "2_2") (pintype "passive"))
    )
    (net (code "38") (name "Net-(C15-C2)") (class "Default")
      (node (ref "C15") (pin "2") (pinfunction "C2_2") (pintype "passive"))
      (node (ref "IC1") (pin "3") (pinfunction "IN+_3") (pintype "input"))
      (node (ref "R19") (pin "2") (pinfunction "R2_2") (pintype "passive"))
      (node (ref "R2") (pin "1") (pinfunction "R1_1") (pintype "passive"))
    )
    (net (code "39") (name "Net-(C19-C1)") (class "Default")
      (node (ref "C19") (pin "2") (pinfunction "C1_2") (pintype "passive"))
      (node (ref "U$8") (pin "31") (pinfunction "XC1_31") (pintype "bidirectional"))
      (node (ref "XTAL1") (pin "3") (pinfunction "3_3") (pintype "passive"))
    )
    (net (code "40") (name "Net-(C21-C2)") (class "Default")
      (node (ref "C21") (pin "2") (pinfunction "C2_2") (pintype "passive"))
      (node (ref "U$8") (pin "4") (pinfunction "DEC2_4") (pintype "bidirectional"))
    )
    (net (code "41") (name "Net-(C24-C2)") (class "Default")
      (node (ref "C24") (pin "1") (pinfunction "C2_1") (pintype "passive"))
      (node (ref "U$8") (pin "3") (pinfunction "DEC1_3") (pintype "bidirectional"))
    )
    (net (code "42") (name "Net-(R1-R1)") (class "Default")
      (node (ref "R1") (pin "1") (pinfunction "R1_1") (pintype "passive"))
      (node (ref "U$1") (pin "2") (pinfunction "EN_2") (pintype "bidirectional"))
      (node (ref "U$2") (pin "2") (pinfunction "EN_2") (pintype "bidirectional"))
    )
    (net (code "43") (name "Net-(R9-R2)") (class "Default")
      (node (ref "R9") (pin "2") (pinfunction "R2_2") (pintype "passive"))
      (node (ref "U$8") (pin "25") (pinfunction "IREF_25") (pintype "bidirectional"))
    )
    (net (code "44") (name "Net-(U$8-ANT1)") (class "Default")
      (node (ref "FB1") (pin "2") (pinfunction "2_2") (pintype "passive"))
      (node (ref "FB2") (pin "2") (pinfunction "2_2") (pintype "passive"))
      (node (ref "U$8") (pin "21") (pinfunction "ANT1_21") (pintype "bidirectional"))
    )
    (net (code "45") (name "Net-(U$8-ANT2)") (class "Default")
      (node (ref "FB2") (pin "1") (pinfunction "1_1") (pintype "passive"))
      (node (ref "FB3") (pin "1") (pinfunction "1_1") (pintype "passive"))
      (node (ref "U$8") (pin "22") (pinfunction "ANT2_22") (pintype "bidirectional"))
    )
    (net (code "46") (name "VCC") (class "Default")
      (node (ref "C13") (pin "2") (pinfunction "C2_2") (pintype "passive"))
      (node (ref "C2") (pin "2") (pinfunction "C2_2") (pintype "passive"))
      (node (ref "C27") (pin "2") (pinfunction "C2_2") (pintype "passive"))
      (node (ref "C28") (pin "2") (pinfunction "C2_2") (pintype "passive"))
      (node (ref "C3") (pin "1") (pinfunction "C2_1") (pintype "passive"))
      (node (ref "C4") (pin "2") (pinfunction "C2_2") (pintype "passive"))
      (node (ref "C7") (pin "2") (pinfunction "C2_2") (pintype "passive"))
      (node (ref "R11") (pin "1") (pinfunction "R1_1") (pintype "passive"))
      (node (ref "R16") (pin "2") (pinfunction "R2_2") (pintype "passive"))
      (node (ref "R9") (pin "1") (pinfunction "R1_1") (pintype "passive"))
      (node (ref "U$1") (pin "4") (pinfunction "OUT_4") (pintype "bidirectional"))
      (node (ref "U$3") (pin "12") (pinfunction "D_VDD_12") (pintype "bidirectional"))
      (node (ref "U$3") (pin "24") (pinfunction "D_VDD_24") (pintype "bidirectional"))
      (node (ref "U$8") (pin "2") (pinfunction "VDD1_2") (pintype "bidirectional"))
      (node (ref "U$8") (pin "24") (pinfunction "VDD3_24") (pintype "bidirectional"))
      (node (ref "U$8") (pin "27") (pinfunction "VDD4_27") (pintype "bidirectional"))
      (node (ref "U$8") (pin "9") (pinfunction "VDD2_9") (pintype "bidirectional"))
      (node (ref "U1") (pin "12") (pinfunction "VDD_12") (pintype "power_in"))
    )
    (net (code "47") (name "VDD") (class "Default")
      (node (ref "C1") (pin "2") (pinfunction "C2_2") (pintype "passive"))
      (node (ref "C23") (pin "2") (pinfunction "C2_2") (pintype "passive"))
      (node (ref "C8") (pin "2") (pinfunction "C2_2") (pintype "passive"))
      (node (ref "IC1") (pin "8") (pinfunction "VCC+_8") (pintype "power_in"))
      (node (ref "IC2") (pin "2") (pinfunction "VCC+_2") (pintype "power_in"))
      (node (ref "PH4") (pin "P$1") (pinfunction "1_P$1") (pintype "bidirectional"))
      (node (ref "R19") (pin "1") (pinfunction "R1_1") (pintype "passive"))
      (node (ref "U$2") (pin "4") (pinfunction "OUT_4") (pintype "bidirectional"))
      (node (ref "U$3") (pin "11") (pinfunction "A_VDD_11") (pintype "bidirectional"))
      (node (ref "U$3") (pin "25") (pinfunction "A_VDD_25") (pintype "bidirectional"))
    )
    (net (code "48") (name "unconnected-(ANTENNA_CHIP-Pad2)") (class "Default")
      (node (ref "ANTENNA_CHIP") (pin "2") (pinfunction "2_2") (pintype "passive"))
    )
    (net (code "49") (name "unconnected-(U$8-P0.0-Pad32)") (class "Default")
      (node (ref "U$8") (pin "32") (pinfunction "P0.0_32") (pintype "bidirectional"))
    )
    (net (code "50") (name "unconnected-(U$8-P0.1-Pad1)") (class "Default")
      (node (ref "U$8") (pin "1") (pinfunction "P0.1_1") (pintype "bidirectional"))
    )
    (net (code "51") (name "unconnected-(U$8-P0.2-Pad5)") (class "Default")
      (node (ref "U$8") (pin "5") (pinfunction "P0.2_5") (pintype "bidirectional"))
    )
    (net (code "52") (name "unconnected-(U$8-P0.3-Pad7)") (class "Default")
      (node (ref "U$8") (pin "7") (pinfunction "P0.3_7") (pintype "bidirectional"))
    )
    (net (code "53") (name "unconnected-(U$8-P1.0-Pad14)") (class "Default")
      (node (ref "U$8") (pin "14") (pinfunction "P1.0_14") (pintype "bidirectional"))
    )
    (net (code "54") (name "unconnected-(U$8-P1.1-Pad15)") (class "Default")
      (node (ref "U$8") (pin "15") (pinfunction "P1.1_15") (pintype "bidirectional"))
    )
    (net (code "55") (name "unconnected-(U$8-PROG-Pad6)") (class "Default")
      (node (ref "U$8") (pin "6") (pinfunction "PROG_6") (pintype "bidirectional"))
    )
    (net (code "56") (name "unconnected-(U$8-RESET-Pad19)") (class "Default")
      (node (ref "U$8") (pin "19") (pinfunction "RESET_19") (pintype "bidirectional"))
    )
  )
)
